# PLD.net
KiCad netlist of a schematic drawn in Altium Designer
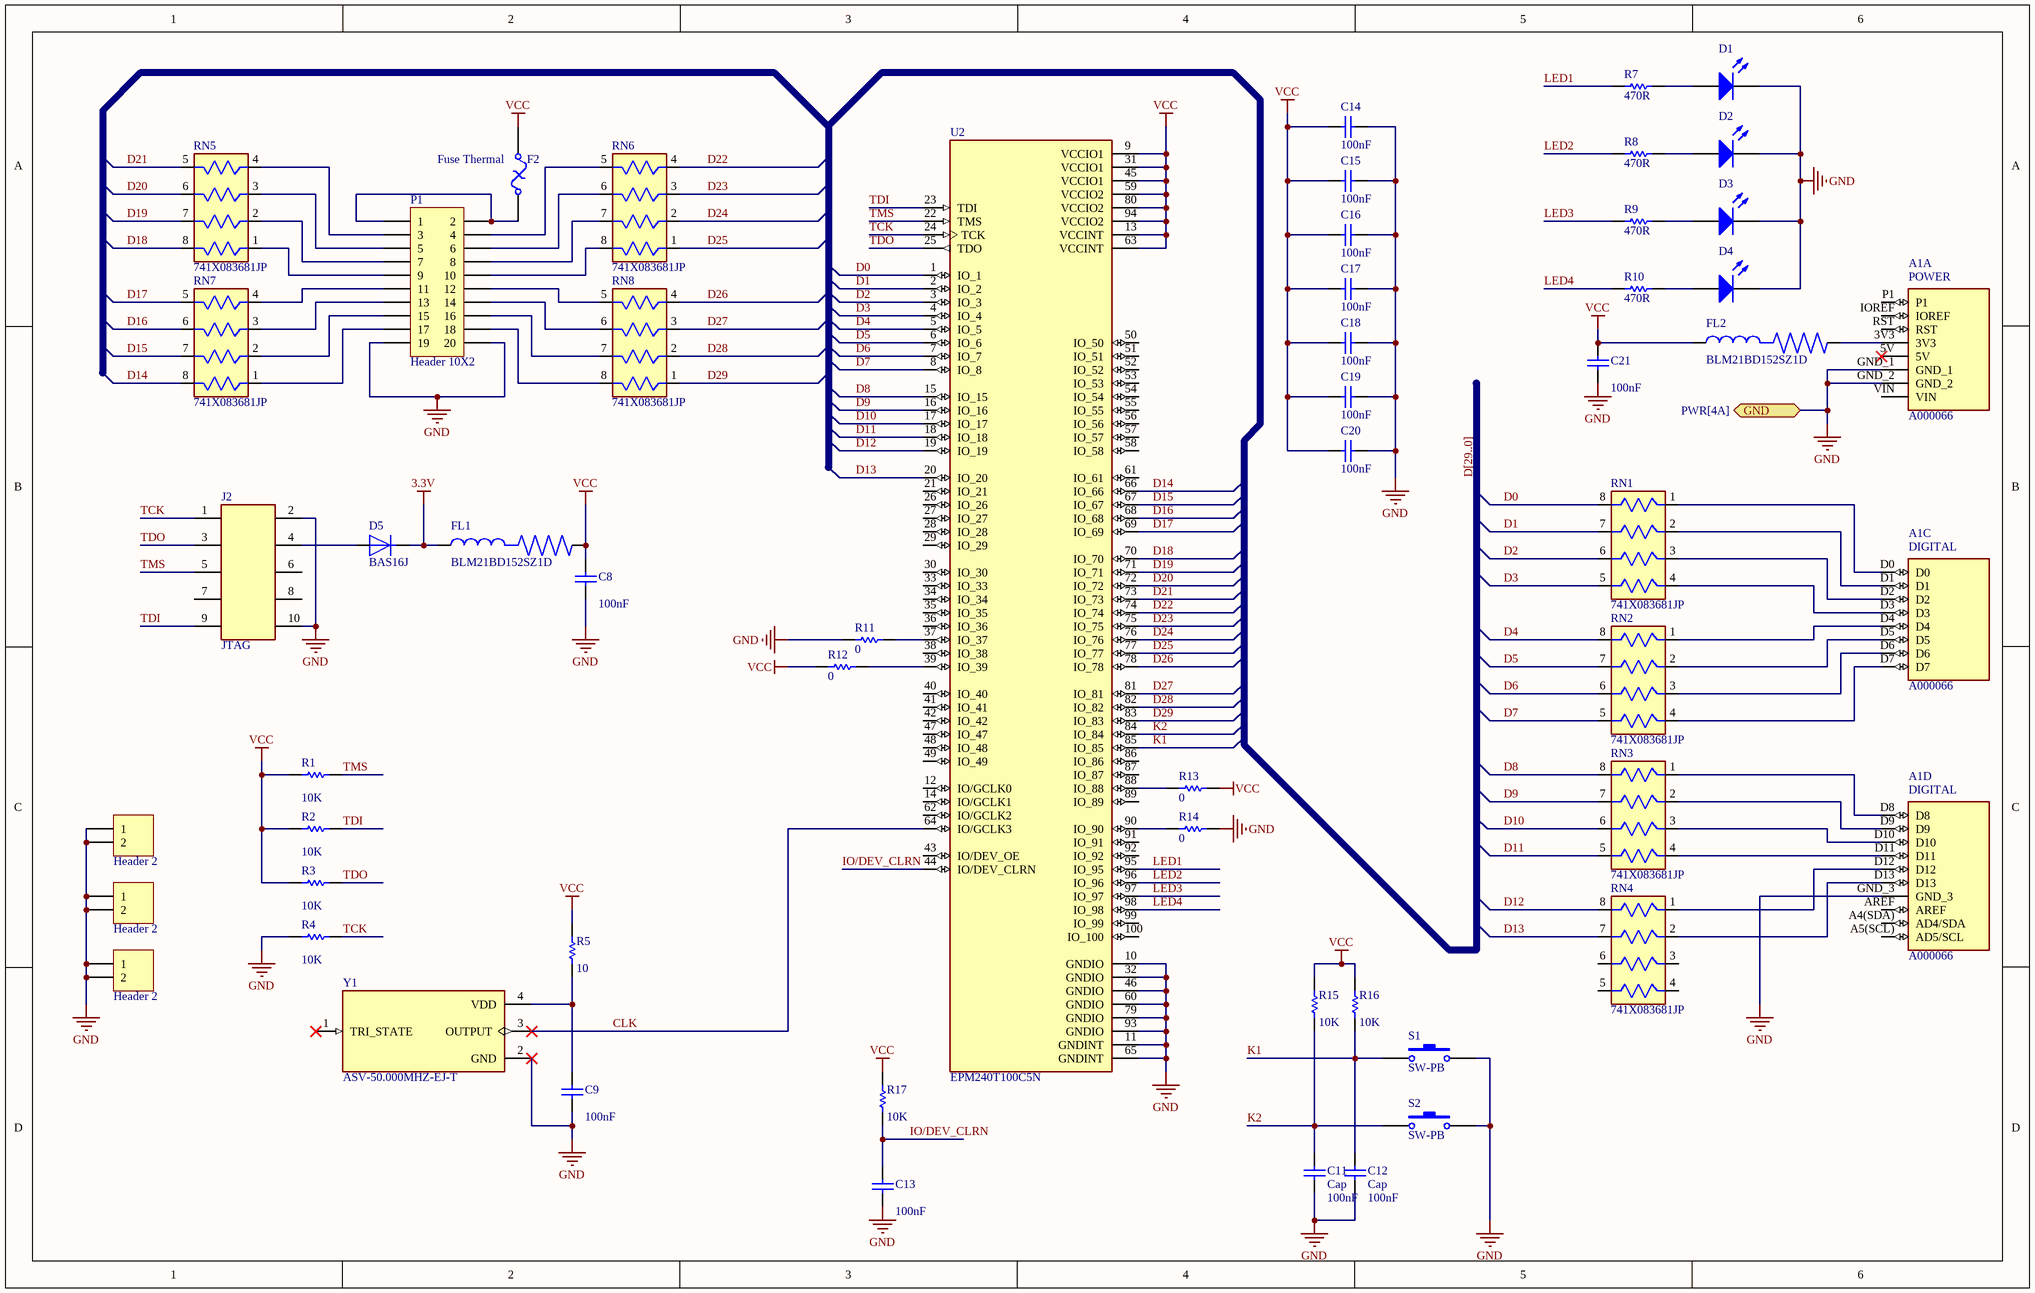
[diagram p0: PLD.SchDoc]

(export (version "E")
  (design (tool "Eeschema 10.0.6"))
  (components
    (comp (ref "A1")
      (value "A000066")
      (footprint "ARDUINO_A000066")
      (description "Microcontroller board based on the ATmega328P")
      (fields (field (name "MP") "ARDUINO UNO REV3 DEVELOPMENT BOARD") (field (name "MF") "Arduino"))
      (libsource (lib "A000066") (part "A000066"))
    )
    (comp (ref "C8")
      (value "100nF")
      (footprint "CAPC1608X90")
      (description "Capacitor")
      (fields (field (name "Comment") "Cap") (field (name "PUBLISHER") "Altium Limited"))
      (libsource (lib "Miscellaneous Devices") (part "Cap"))
    )
    (comp (ref "C9")
      (value "100nF")
      (footprint "CAPC1608X90")
      (description "Capacitor")
      (fields (field (name "Comment") "Cap") (field (name "PUBLISHER") "Altium Limited"))
      (libsource (lib "Miscellaneous Devices") (part "Cap"))
    )
    (comp (ref "C11")
      (value "Cap")
      (footprint "WCAP-CSGP_885012105016")
      (description "Capacitor")
      (fields (field (name "ALTIUM_VALUE") "100nF") (field (name "PUBLISHER") "Altium Limited"))
      (libsource (lib "Miscellaneous Devices") (part "Cap"))
    )
    (comp (ref "C12")
      (value "Cap")
      (footprint "WCAP-CSGP_885012105016")
      (description "Capacitor")
      (fields (field (name "ALTIUM_VALUE") "100nF") (field (name "PUBLISHER") "Altium Limited"))
      (libsource (lib "Miscellaneous Devices") (part "Cap"))
    )
    (comp (ref "C13")
      (value "100nF")
      (footprint "WCAP-CSGP_885012105016")
      (description "Capacitor")
      (fields (field (name "Comment") "Cap") (field (name "PUBLISHER") "Altium Limited"))
      (libsource (lib "Miscellaneous Devices") (part "Cap"))
    )
    (comp (ref "C14")
      (value "100nF")
      (footprint "WCAP-CSGP_885012105016")
      (description "Capacitor")
      (fields (field (name "Comment") "Cap") (field (name "PUBLISHER") "Altium Limited"))
      (libsource (lib "Miscellaneous Devices") (part "Cap"))
    )
    (comp (ref "C15")
      (value "100nF")
      (footprint "WCAP-CSGP_885012105016")
      (description "Capacitor")
      (fields (field (name "Comment") "Cap") (field (name "PUBLISHER") "Altium Limited"))
      (libsource (lib "Miscellaneous Devices") (part "Cap"))
    )
    (comp (ref "C16")
      (value "100nF")
      (footprint "WCAP-CSGP_885012105016")
      (description "Capacitor")
      (fields (field (name "Comment") "Cap") (field (name "PUBLISHER") "Altium Limited"))
      (libsource (lib "Miscellaneous Devices") (part "Cap"))
    )
    (comp (ref "C17")
      (value "100nF")
      (footprint "WCAP-CSGP_885012105016")
      (description "Capacitor")
      (fields (field (name "Comment") "Cap") (field (name "PUBLISHER") "Altium Limited"))
      (libsource (lib "Miscellaneous Devices") (part "Cap"))
    )
    (comp (ref "C18")
      (value "100nF")
      (footprint "WCAP-CSGP_885012105016")
      (description "Capacitor")
      (fields (field (name "Comment") "Cap") (field (name "PUBLISHER") "Altium Limited"))
      (libsource (lib "Miscellaneous Devices") (part "Cap"))
    )
    (comp (ref "C19")
      (value "100nF")
      (footprint "WCAP-CSGP_885012105016")
      (description "Capacitor")
      (fields (field (name "Comment") "Cap") (field (name "PUBLISHER") "Altium Limited"))
      (libsource (lib "Miscellaneous Devices") (part "Cap"))
    )
    (comp (ref "C20")
      (value "100nF")
      (footprint "WCAP-CSGP_885012105016")
      (description "Capacitor")
      (fields (field (name "Comment") "Cap") (field (name "PUBLISHER") "Altium Limited"))
      (libsource (lib "Miscellaneous Devices") (part "Cap"))
    )
    (comp (ref "C21")
      (value "100nF")
      (footprint "CAPC1608X90")
      (description "Capacitor")
      (fields (field (name "Comment") "Cap") (field (name "PUBLISHER") "Altium Limited"))
      (libsource (lib "Miscellaneous Devices") (part "Cap"))
    )
    (comp (ref "D1")
      (value "LED0")
      (footprint "CAPC1608X90")
      (description "Typical INFRARED GaAs LED")
      (fields (field (name "PUBLISHER") "Altium Limited"))
      (libsource (lib "Miscellaneous Devices") (part "LED0"))
    )
    (comp (ref "D2")
      (value "LED0")
      (footprint "CAPC1608X90")
      (description "Typical INFRARED GaAs LED")
      (fields (field (name "PUBLISHER") "Altium Limited"))
      (libsource (lib "Miscellaneous Devices") (part "LED0"))
    )
    (comp (ref "D3")
      (value "LED0")
      (footprint "CAPC1608X90")
      (description "Typical INFRARED GaAs LED")
      (fields (field (name "PUBLISHER") "Altium Limited"))
      (libsource (lib "Miscellaneous Devices") (part "LED0"))
    )
    (comp (ref "D4")
      (value "LED0")
      (footprint "CAPC1608X90")
      (description "Typical INFRARED GaAs LED")
      (fields (field (name "PUBLISHER") "Altium Limited"))
      (libsource (lib "Miscellaneous Devices") (part "LED0"))
    )
    (comp (ref "D5")
      (value "BAS16J")
      (footprint "SOD323F")
      (description "Diode Standard 100V 250mA _DC_ Surface Mount SOD-323F")
      (fields (field (name "MF") "Nexperia USA"))
      (libsource (lib "BAS16J") (part "BAS16J"))
    )
    (comp (ref "F2")
      (value "Fuse Thermal")
      (footprint "C1206")
      (description "Thermal Fuse")
      (fields (field (name "PUBLISHER") "Altium Limited"))
      (libsource (lib "Miscellaneous Devices") (part "Fuse Thermal"))
    )
    (comp (ref "FL1")
      (value "BLM21BD152SZ1D")
      (footprint "C1206")
      (description "1 Ferrite Bead 0805 (2012 Metric) 250mA 450mOhm")
      (fields (field (name "MF") "Murata"))
      (libsource (lib "FB0603") (part "BLM21BD152SZ1D"))
    )
    (comp (ref "FL2")
      (value "BLM21BD152SZ1D")
      (footprint "C1206")
      (description "1 Ferrite Bead 0805 (2012 Metric) 250mA 450mOhm")
      (fields (field (name "MF") "Murata"))
      (libsource (lib "FB0603") (part "BLM21BD152SZ1D"))
    )
    (comp (ref "H2")
      (value "Header 2")
      (footprint "HDR1X2")
      (description "Header, 2-Pin")
      (fields (field (name "PUBLISHER") "Altium Limited"))
      (libsource (lib "Miscellaneous Connectors") (part "Header 2"))
    )
    (comp (ref "H3")
      (value "Header 2")
      (footprint "HDR1X2")
      (description "Header, 2-Pin")
      (fields (field (name "PUBLISHER") "Altium Limited"))
      (libsource (lib "Miscellaneous Connectors") (part "Header 2"))
    )
    (comp (ref "H4")
      (value "Header 2")
      (footprint "HDR1X2")
      (description "Header, 2-Pin")
      (fields (field (name "PUBLISHER") "Altium Limited"))
      (libsource (lib "Miscellaneous Connectors") (part "Header 2"))
    )
    (comp (ref "J2")
      (value "JTAG")
      (footprint "61201021621")
      (description "Connector Header Through Hole 10 position 0.100 _2.54mm_")
      (fields (field (name "MP") "61201021621") (field (name "MF") "Wurth Electronics"))
      (libsource (lib "61201021621") (part "61201021621"))
    )
    (comp (ref "P1")
      (value "Header 10X2")
      (footprint "2002132110020C4LF")
      (description "Header, 10-Pin, Dual row")
      (fields (field (name "PUBLISHER") "Altium Limited"))
      (libsource (lib "Miscellaneous Connectors") (part "Header 10X2"))
    )
    (comp (ref "R1")
      (value "10K")
      (footprint "CAPC1608X90")
      (description "Resistor")
      (fields (field (name "Comment") "Res1") (field (name "PUBLISHER") "Altium Limited"))
      (libsource (lib "Miscellaneous Devices") (part "Res1"))
    )
    (comp (ref "R2")
      (value "10K")
      (footprint "CAPC1608X90")
      (description "Resistor")
      (fields (field (name "Comment") "Res1") (field (name "PUBLISHER") "Altium Limited"))
      (libsource (lib "Miscellaneous Devices") (part "Res1"))
    )
    (comp (ref "R3")
      (value "10K")
      (footprint "CAPC1608X90")
      (description "Resistor")
      (fields (field (name "Comment") "Res1") (field (name "PUBLISHER") "Altium Limited"))
      (libsource (lib "Miscellaneous Devices") (part "Res1"))
    )
    (comp (ref "R4")
      (value "10K")
      (footprint "CAPC1608X90")
      (description "Resistor")
      (fields (field (name "Comment") "Res1") (field (name "PUBLISHER") "Altium Limited"))
      (libsource (lib "Miscellaneous Devices") (part "Res1"))
    )
    (comp (ref "R5")
      (value "10")
      (footprint "CAPC1608X90")
      (description "Resistor")
      (fields (field (name "Comment") "Res1") (field (name "PUBLISHER") "Altium Limited"))
      (libsource (lib "Miscellaneous Devices") (part "Res1"))
    )
    (comp (ref "R7")
      (value "470R")
      (footprint "CAPC1608X90")
      (description "Resistor")
      (fields (field (name "Comment") "Res1") (field (name "PUBLISHER") "Altium Limited"))
      (libsource (lib "Miscellaneous Devices") (part "Res1"))
    )
    (comp (ref "R8")
      (value "470R")
      (footprint "CAPC1608X90")
      (description "Resistor")
      (fields (field (name "Comment") "Res1") (field (name "PUBLISHER") "Altium Limited"))
      (libsource (lib "Miscellaneous Devices") (part "Res1"))
    )
    (comp (ref "R9")
      (value "470R")
      (footprint "CAPC1608X90")
      (description "Resistor")
      (fields (field (name "Comment") "Res1") (field (name "PUBLISHER") "Altium Limited"))
      (libsource (lib "Miscellaneous Devices") (part "Res1"))
    )
    (comp (ref "R10")
      (value "470R")
      (footprint "CAPC1608X90")
      (description "Resistor")
      (fields (field (name "Comment") "Res1") (field (name "PUBLISHER") "Altium Limited"))
      (libsource (lib "Miscellaneous Devices") (part "Res1"))
    )
    (comp (ref "R11")
      (value "0")
      (footprint "WCAP-CSGP_885012105016")
      (description "Resistor")
      (fields (field (name "Comment") "Res1") (field (name "PUBLISHER") "Altium Limited"))
      (libsource (lib "Miscellaneous Devices") (part "Res1"))
    )
    (comp (ref "R12")
      (value "0")
      (footprint "WCAP-CSGP_885012105016")
      (description "Resistor")
      (fields (field (name "Comment") "Res1") (field (name "PUBLISHER") "Altium Limited"))
      (libsource (lib "Miscellaneous Devices") (part "Res1"))
    )
    (comp (ref "R13")
      (value "0")
      (footprint "WCAP-CSGP_885012105016")
      (description "Resistor")
      (fields (field (name "Comment") "Res1") (field (name "PUBLISHER") "Altium Limited"))
      (libsource (lib "Miscellaneous Devices") (part "Res1"))
    )
    (comp (ref "R14")
      (value "0")
      (footprint "WCAP-CSGP_885012105016")
      (description "Resistor")
      (fields (field (name "Comment") "Res1") (field (name "PUBLISHER") "Altium Limited"))
      (libsource (lib "Miscellaneous Devices") (part "Res1"))
    )
    (comp (ref "R15")
      (value "10K")
      (footprint "WCAP-CSGP_885012105016")
      (description "Resistor")
      (fields (field (name "Comment") "Res1") (field (name "PUBLISHER") "Altium Limited"))
      (libsource (lib "Miscellaneous Devices") (part "Res1"))
    )
    (comp (ref "R16")
      (value "10K")
      (footprint "WCAP-CSGP_885012105016")
      (description "Resistor")
      (fields (field (name "Comment") "Res1") (field (name "PUBLISHER") "Altium Limited"))
      (libsource (lib "Miscellaneous Devices") (part "Res1"))
    )
    (comp (ref "R17")
      (value "10K")
      (footprint "WCAP-CSGP_885012105016")
      (description "Resistor")
      (fields (field (name "Comment") "Res1") (field (name "PUBLISHER") "Altium Limited"))
      (libsource (lib "Miscellaneous Devices") (part "Res1"))
    )
    (comp (ref "RN1")
      (value "741X083681JP")
      (footprint "RESCAXS50P200X100X45_8N")
      (description "Resistor Networks & Arrays 680ohms 5% Isolated")
      (fields (field (name "MF") "CTS Components"))
      (libsource (lib "741X083681JP") (part "741X083681JP"))
    )
    (comp (ref "RN2")
      (value "741X083681JP")
      (footprint "RESCAXS50P200X100X45_8N")
      (description "Resistor Networks & Arrays 680ohms 5% Isolated")
      (fields (field (name "MF") "CTS Components"))
      (libsource (lib "741X083681JP") (part "741X083681JP"))
    )
    (comp (ref "RN3")
      (value "741X083681JP")
      (footprint "RESCAXS50P200X100X45_8N")
      (description "Resistor Networks & Arrays 680ohms 5% Isolated")
      (fields (field (name "MF") "CTS Components"))
      (libsource (lib "741X083681JP") (part "741X083681JP"))
    )
    (comp (ref "RN4")
      (value "741X083681JP")
      (footprint "RESCAXS50P200X100X45_8N")
      (description "Resistor Networks & Arrays 680ohms 5% Isolated")
      (fields (field (name "MF") "CTS Components"))
      (libsource (lib "741X083681JP") (part "741X083681JP"))
    )
    (comp (ref "RN5")
      (value "741X083681JP")
      (footprint "RESCAXS50P200X100X45_8N")
      (description "Resistor Networks & Arrays 680ohms 5% Isolated")
      (fields (field (name "MF") "CTS Components"))
      (libsource (lib "") (part "741X083681JP_1"))
    )
    (comp (ref "RN6")
      (value "741X083681JP")
      (footprint "RESCAXS50P200X100X45_8N")
      (description "Resistor Networks & Arrays 680ohms 5% Isolated")
      (fields (field (name "MF") "CTS Components"))
      (libsource (lib "") (part "741X083681JP_1"))
    )
    (comp (ref "RN7")
      (value "741X083681JP")
      (footprint "RESCAXS50P200X100X45_8N")
      (description "Resistor Networks & Arrays 680ohms 5% Isolated")
      (fields (field (name "MF") "CTS Components"))
      (libsource (lib "") (part "741X083681JP_1"))
    )
    (comp (ref "RN8")
      (value "741X083681JP")
      (footprint "RESCAXS50P200X100X45_8N")
      (description "Resistor Networks & Arrays 680ohms 5% Isolated")
      (fields (field (name "MF") "CTS Components"))
      (libsource (lib "") (part "741X083681JP_1"))
    )
    (comp (ref "S1")
      (value "SW-PB")
      (footprint "SW_4.5X4.5")
      (description "Switch")
      (fields (field (name "PUBLISHER") "Altium Limited"))
      (libsource (lib "Miscellaneous Devices") (part "SW-PB"))
    )
    (comp (ref "S2")
      (value "SW-PB")
      (footprint "SW_4.5X4.5")
      (description "Switch")
      (fields (field (name "PUBLISHER") "Altium Limited"))
      (libsource (lib "Miscellaneous Devices") (part "SW-PB"))
    )
    (comp (ref "U2")
      (value "EPM240T100C5N")
      (footprint "QFP50P1600X1600X120-100N")
      (description "IC CPLD 192MC 4.7NS 100TQFP")
      (fields (field (name "MF") "Intel"))
      (libsource (lib "EPM240T100C5N") (part "EPM240T100C5N"))
    )
    (comp (ref "Y1")
      (value "ASV-50.000MHZ-EJ-T")
      (footprint "XTAL_ASV-50.000MHZ-EJ-T")
      (libsource (lib "ASV-50.000MHZ-EJ-T") (part "ASV-50.000MHZ-EJ-T"))
    )
  )
  (nets
    (net (code "1") (name "/CLK") (class "Default")
      (node (ref "U2") (pin "64") (pinfunction "IO/GCLK3_64") (pintype "bidirectional"))
      (node (ref "Y1") (pin "3") (pinfunction "OUTPUT_3") (pintype "output"))
    )
    (net (code "2") (name "/D0") (class "Default")
      (node (ref "RN1") (pin "8") (pinfunction "8_8") (pintype "passive"))
      (node (ref "U2") (pin "1") (pinfunction "IO_1_1") (pintype "bidirectional"))
    )
    (net (code "3") (name "/D1") (class "Default")
      (node (ref "RN1") (pin "7") (pinfunction "7_7") (pintype "passive"))
      (node (ref "U2") (pin "2") (pinfunction "IO_2_2") (pintype "bidirectional"))
    )
    (net (code "4") (name "/D2") (class "Default")
      (node (ref "RN1") (pin "6") (pinfunction "6_6") (pintype "passive"))
      (node (ref "U2") (pin "3") (pinfunction "IO_3_3") (pintype "bidirectional"))
    )
    (net (code "5") (name "/D3") (class "Default")
      (node (ref "RN1") (pin "5") (pinfunction "5_5") (pintype "passive"))
      (node (ref "U2") (pin "4") (pinfunction "IO_4_4") (pintype "bidirectional"))
    )
    (net (code "6") (name "/D4") (class "Default")
      (node (ref "RN2") (pin "8") (pinfunction "8_8") (pintype "passive"))
      (node (ref "U2") (pin "5") (pinfunction "IO_5_5") (pintype "bidirectional"))
    )
    (net (code "7") (name "/D5") (class "Default")
      (node (ref "RN2") (pin "7") (pinfunction "7_7") (pintype "passive"))
      (node (ref "U2") (pin "6") (pinfunction "IO_6_6") (pintype "bidirectional"))
    )
    (net (code "8") (name "/D6") (class "Default")
      (node (ref "RN2") (pin "6") (pinfunction "6_6") (pintype "passive"))
      (node (ref "U2") (pin "7") (pinfunction "IO_7_7") (pintype "bidirectional"))
    )
    (net (code "9") (name "/D7") (class "Default")
      (node (ref "RN2") (pin "5") (pinfunction "5_5") (pintype "passive"))
      (node (ref "U2") (pin "8") (pinfunction "IO_8_8") (pintype "bidirectional"))
    )
    (net (code "10") (name "/D8") (class "Default")
      (node (ref "RN3") (pin "8") (pinfunction "8_8") (pintype "passive"))
      (node (ref "U2") (pin "15") (pinfunction "IO_15_15") (pintype "bidirectional"))
    )
    (net (code "11") (name "/D9") (class "Default")
      (node (ref "RN3") (pin "7") (pinfunction "7_7") (pintype "passive"))
      (node (ref "U2") (pin "16") (pinfunction "IO_16_16") (pintype "bidirectional"))
    )
    (net (code "12") (name "/D10") (class "Default")
      (node (ref "RN3") (pin "6") (pinfunction "6_6") (pintype "passive"))
      (node (ref "U2") (pin "17") (pinfunction "IO_17_17") (pintype "bidirectional"))
    )
    (net (code "13") (name "/D11") (class "Default")
      (node (ref "RN3") (pin "5") (pinfunction "5_5") (pintype "passive"))
      (node (ref "U2") (pin "18") (pinfunction "IO_18_18") (pintype "bidirectional"))
    )
    (net (code "14") (name "/D12") (class "Default")
      (node (ref "RN4") (pin "8") (pinfunction "8_8") (pintype "passive"))
      (node (ref "U2") (pin "19") (pinfunction "IO_19_19") (pintype "bidirectional"))
    )
    (net (code "15") (name "/D13") (class "Default")
      (node (ref "RN4") (pin "7") (pinfunction "7_7") (pintype "passive"))
      (node (ref "U2") (pin "20") (pinfunction "IO_20_20") (pintype "bidirectional"))
    )
    (net (code "16") (name "/D14") (class "Default")
      (node (ref "RN7") (pin "8") (pinfunction "8_8") (pintype "passive"))
      (node (ref "U2") (pin "66") (pinfunction "IO_66_66") (pintype "bidirectional"))
    )
    (net (code "17") (name "/D15") (class "Default")
      (node (ref "RN7") (pin "7") (pinfunction "7_7") (pintype "passive"))
      (node (ref "U2") (pin "67") (pinfunction "IO_67_67") (pintype "bidirectional"))
    )
    (net (code "18") (name "/D16") (class "Default")
      (node (ref "RN7") (pin "6") (pinfunction "6_6") (pintype "passive"))
      (node (ref "U2") (pin "68") (pinfunction "IO_68_68") (pintype "bidirectional"))
    )
    (net (code "19") (name "/D17") (class "Default")
      (node (ref "RN7") (pin "5") (pinfunction "5_5") (pintype "passive"))
      (node (ref "U2") (pin "69") (pinfunction "IO_69_69") (pintype "bidirectional"))
    )
    (net (code "20") (name "/D18") (class "Default")
      (node (ref "RN5") (pin "8") (pinfunction "8_8") (pintype "passive"))
      (node (ref "U2") (pin "70") (pinfunction "IO_70_70") (pintype "bidirectional"))
    )
    (net (code "21") (name "/D19") (class "Default")
      (node (ref "RN5") (pin "7") (pinfunction "7_7") (pintype "passive"))
      (node (ref "U2") (pin "71") (pinfunction "IO_71_71") (pintype "bidirectional"))
    )
    (net (code "22") (name "/D20") (class "Default")
      (node (ref "RN5") (pin "6") (pinfunction "6_6") (pintype "passive"))
      (node (ref "U2") (pin "72") (pinfunction "IO_72_72") (pintype "bidirectional"))
    )
    (net (code "23") (name "/D21") (class "Default")
      (node (ref "RN5") (pin "5") (pinfunction "5_5") (pintype "passive"))
      (node (ref "U2") (pin "73") (pinfunction "IO_73_73") (pintype "bidirectional"))
    )
    (net (code "24") (name "/D22") (class "Default")
      (node (ref "RN6") (pin "4") (pinfunction "4_4") (pintype "passive"))
      (node (ref "U2") (pin "74") (pinfunction "IO_74_74") (pintype "bidirectional"))
    )
    (net (code "25") (name "/D23") (class "Default")
      (node (ref "RN6") (pin "3") (pinfunction "3_3") (pintype "passive"))
      (node (ref "U2") (pin "75") (pinfunction "IO_75_75") (pintype "bidirectional"))
    )
    (net (code "26") (name "/D24") (class "Default")
      (node (ref "RN6") (pin "2") (pinfunction "2_2") (pintype "passive"))
      (node (ref "U2") (pin "76") (pinfunction "IO_76_76") (pintype "bidirectional"))
    )
    (net (code "27") (name "/D25") (class "Default")
      (node (ref "RN6") (pin "1") (pinfunction "1_1") (pintype "passive"))
      (node (ref "U2") (pin "77") (pinfunction "IO_77_77") (pintype "bidirectional"))
    )
    (net (code "28") (name "/D26") (class "Default")
      (node (ref "RN8") (pin "4") (pinfunction "4_4") (pintype "passive"))
      (node (ref "U2") (pin "78") (pinfunction "IO_78_78") (pintype "bidirectional"))
    )
    (net (code "29") (name "/D27") (class "Default")
      (node (ref "RN8") (pin "3") (pinfunction "3_3") (pintype "passive"))
      (node (ref "U2") (pin "81") (pinfunction "IO_81_81") (pintype "bidirectional"))
    )
    (net (code "30") (name "/D28") (class "Default")
      (node (ref "RN8") (pin "2") (pinfunction "2_2") (pintype "passive"))
      (node (ref "U2") (pin "82") (pinfunction "IO_82_82") (pintype "bidirectional"))
    )
    (net (code "31") (name "/D29") (class "Default")
      (node (ref "RN8") (pin "1") (pinfunction "1_1") (pintype "passive"))
      (node (ref "U2") (pin "83") (pinfunction "IO_83_83") (pintype "bidirectional"))
    )
    (net (code "33") (name "/IO{slash}DEV_CLRN") (class "Default")
      (node (ref "C13") (pin "2") (pinfunction "2_2") (pintype "passive"))
      (node (ref "R17") (pin "1") (pinfunction "1_1") (pintype "passive"))
      (node (ref "U2") (pin "44") (pinfunction "IO/DEV_CLRN_44") (pintype "bidirectional"))
    )
    (net (code "34") (name "/K1") (class "Default")
      (node (ref "C12") (pin "2") (pinfunction "2_2") (pintype "passive"))
      (node (ref "R16") (pin "1") (pinfunction "1_1") (pintype "passive"))
      (node (ref "S1") (pin "1") (pinfunction "1_1") (pintype "passive"))
      (node (ref "U2") (pin "85") (pinfunction "IO_85_85") (pintype "bidirectional"))
    )
    (net (code "35") (name "/K2") (class "Default")
      (node (ref "C11") (pin "2") (pinfunction "2_2") (pintype "passive"))
      (node (ref "R15") (pin "1") (pinfunction "1_1") (pintype "passive"))
      (node (ref "S2") (pin "1") (pinfunction "1_1") (pintype "passive"))
      (node (ref "U2") (pin "84") (pinfunction "IO_84_84") (pintype "bidirectional"))
    )
    (net (code "36") (name "/LED1") (class "Default")
      (node (ref "R7") (pin "2") (pinfunction "2_2") (pintype "passive"))
      (node (ref "U2") (pin "95") (pinfunction "IO_95_95") (pintype "bidirectional"))
    )
    (net (code "37") (name "/LED2") (class "Default")
      (node (ref "R8") (pin "2") (pinfunction "2_2") (pintype "passive"))
      (node (ref "U2") (pin "96") (pinfunction "IO_96_96") (pintype "bidirectional"))
    )
    (net (code "38") (name "/LED3") (class "Default")
      (node (ref "R9") (pin "2") (pinfunction "2_2") (pintype "passive"))
      (node (ref "U2") (pin "97") (pinfunction "IO_97_97") (pintype "bidirectional"))
    )
    (net (code "39") (name "/LED4") (class "Default")
      (node (ref "R10") (pin "2") (pinfunction "2_2") (pintype "passive"))
      (node (ref "U2") (pin "98") (pinfunction "IO_98_98") (pintype "bidirectional"))
    )
    (net (code "40") (name "/TCK") (class "Default")
      (node (ref "J2") (pin "1") (pinfunction "1_1") (pintype "passive"))
      (node (ref "R4") (pin "2") (pinfunction "2_2") (pintype "passive"))
      (node (ref "U2") (pin "24") (pinfunction "TCK_24") (pintype "input"))
    )
    (net (code "41") (name "/TDI") (class "Default")
      (node (ref "J2") (pin "9") (pinfunction "9_9") (pintype "passive"))
      (node (ref "R2") (pin "2") (pinfunction "2_2") (pintype "passive"))
      (node (ref "U2") (pin "23") (pinfunction "TDI_23") (pintype "input"))
    )
    (net (code "42") (name "/TDO") (class "Default")
      (node (ref "J2") (pin "3") (pinfunction "3_3") (pintype "passive"))
      (node (ref "R3") (pin "2") (pinfunction "2_2") (pintype "passive"))
      (node (ref "U2") (pin "25") (pinfunction "TDO_25") (pintype "output"))
    )
    (net (code "43") (name "/TMS") (class "Default")
      (node (ref "J2") (pin "5") (pinfunction "5_5") (pintype "passive"))
      (node (ref "R1") (pin "2") (pinfunction "2_2") (pintype "passive"))
      (node (ref "U2") (pin "22") (pinfunction "TMS_22") (pintype "input"))
    )
    (net (code "44") (name "3.3V") (class "Default")
      (node (ref "D5") (pin "1") (pinfunction "K_1") (pintype "passive"))
      (node (ref "FL1") (pin "1") (pinfunction "1_1") (pintype "passive"))
    )
    (net (code "45") (name "GND") (class "Default")
      (node (ref "A1") (pin "GND_1") (pinfunction "GND_1_GND_1") (pintype "power_in"))
      (node (ref "A1") (pin "GND_2") (pinfunction "GND_2_GND_2") (pintype "power_in"))
      (node (ref "A1") (pin "GND_3") (pinfunction "GND_3_GND_3") (pintype "power_in"))
      (node (ref "C11") (pin "1") (pinfunction "1_1") (pintype "passive"))
      (node (ref "C12") (pin "1") (pinfunction "1_1") (pintype "passive"))
      (node (ref "C13") (pin "1") (pinfunction "1_1") (pintype "passive"))
      (node (ref "C14") (pin "1") (pinfunction "1_1") (pintype "passive"))
      (node (ref "C15") (pin "1") (pinfunction "1_1") (pintype "passive"))
      (node (ref "C16") (pin "1") (pinfunction "1_1") (pintype "passive"))
      (node (ref "C17") (pin "1") (pinfunction "1_1") (pintype "passive"))
      (node (ref "C18") (pin "1") (pinfunction "1_1") (pintype "passive"))
      (node (ref "C19") (pin "1") (pinfunction "1_1") (pintype "passive"))
      (node (ref "C20") (pin "1") (pinfunction "1_1") (pintype "passive"))
      (node (ref "C21") (pin "1") (pinfunction "1_1") (pintype "passive"))
      (node (ref "C8") (pin "1") (pinfunction "1_1") (pintype "passive"))
      (node (ref "C9") (pin "1") (pinfunction "1_1") (pintype "passive"))
      (node (ref "D1") (pin "2") (pinfunction "K_2") (pintype "passive"))
      (node (ref "D2") (pin "2") (pinfunction "K_2") (pintype "passive"))
      (node (ref "D3") (pin "2") (pinfunction "K_2") (pintype "passive"))
      (node (ref "D4") (pin "2") (pinfunction "K_2") (pintype "passive"))
      (node (ref "H2") (pin "1") (pinfunction "1_1") (pintype "passive"))
      (node (ref "H2") (pin "2") (pinfunction "2_2") (pintype "passive"))
      (node (ref "H3") (pin "1") (pinfunction "1_1") (pintype "passive"))
      (node (ref "H3") (pin "2") (pinfunction "2_2") (pintype "passive"))
      (node (ref "H4") (pin "1") (pinfunction "1_1") (pintype "passive"))
      (node (ref "H4") (pin "2") (pinfunction "2_2") (pintype "passive"))
      (node (ref "J2") (pin "10") (pinfunction "10_10") (pintype "passive"))
      (node (ref "J2") (pin "2") (pinfunction "2_2") (pintype "passive"))
      (node (ref "P1") (pin "19") (pinfunction "19_19") (pintype "passive"))
      (node (ref "P1") (pin "20") (pinfunction "20_20") (pintype "passive"))
      (node (ref "R11") (pin "2") (pinfunction "2_2") (pintype "passive"))
      (node (ref "R14") (pin "1") (pinfunction "1_1") (pintype "passive"))
      (node (ref "R4") (pin "1") (pinfunction "1_1") (pintype "passive"))
      (node (ref "S1") (pin "2") (pinfunction "2_2") (pintype "passive"))
      (node (ref "S2") (pin "2") (pinfunction "2_2") (pintype "passive"))
      (node (ref "U2") (pin "10") (pinfunction "GNDIO_10") (pintype "power_in"))
      (node (ref "U2") (pin "11") (pinfunction "GNDINT_11") (pintype "power_in"))
      (node (ref "U2") (pin "32") (pinfunction "GNDIO_32") (pintype "power_in"))
      (node (ref "U2") (pin "46") (pinfunction "GNDIO_46") (pintype "power_in"))
      (node (ref "U2") (pin "60") (pinfunction "GNDIO_60") (pintype "power_in"))
      (node (ref "U2") (pin "65") (pinfunction "GNDINT_65") (pintype "power_in"))
      (node (ref "U2") (pin "79") (pinfunction "GNDIO_79") (pintype "power_in"))
      (node (ref "U2") (pin "93") (pinfunction "GNDIO_93") (pintype "power_in"))
      (node (ref "Y1") (pin "2") (pinfunction "GND_2") (pintype "power_in"))
    )
    (net (code "46") (name "Net-(A1-Pad3V3)") (class "Default")
      (node (ref "A1") (pin "3V3") (pinfunction "3V3_3V3") (pintype "power_in"))
      (node (ref "FL2") (pin "2") (pinfunction "2_2") (pintype "passive"))
    )
    (net (code "47") (name "Net-(A1-PadD0)") (class "Default")
      (node (ref "A1") (pin "D0") (pinfunction "D0_D0") (pintype "bidirectional"))
      (node (ref "RN1") (pin "1") (pinfunction "1_1") (pintype "passive"))
    )
    (net (code "48") (name "Net-(A1-PadD1)") (class "Default")
      (node (ref "A1") (pin "D1") (pinfunction "D1_D1") (pintype "bidirectional"))
      (node (ref "RN1") (pin "2") (pinfunction "2_2") (pintype "passive"))
    )
    (net (code "49") (name "Net-(A1-PadD2)") (class "Default")
      (node (ref "A1") (pin "D2") (pinfunction "D2_D2") (pintype "bidirectional"))
      (node (ref "RN1") (pin "3") (pinfunction "3_3") (pintype "passive"))
    )
    (net (code "50") (name "Net-(A1-PadD3)") (class "Default")
      (node (ref "A1") (pin "D3") (pinfunction "D3_D3") (pintype "bidirectional"))
      (node (ref "RN1") (pin "4") (pinfunction "4_4") (pintype "passive"))
    )
    (net (code "51") (name "Net-(A1-PadD4)") (class "Default")
      (node (ref "A1") (pin "D4") (pinfunction "D4_D4") (pintype "bidirectional"))
      (node (ref "RN2") (pin "1") (pinfunction "1_1") (pintype "passive"))
    )
    (net (code "52") (name "Net-(A1-PadD5)") (class "Default")
      (node (ref "A1") (pin "D5") (pinfunction "D5_D5") (pintype "bidirectional"))
      (node (ref "RN2") (pin "2") (pinfunction "2_2") (pintype "passive"))
    )
    (net (code "53") (name "Net-(A1-PadD6)") (class "Default")
      (node (ref "A1") (pin "D6") (pinfunction "D6_D6") (pintype "bidirectional"))
      (node (ref "RN2") (pin "3") (pinfunction "3_3") (pintype "passive"))
    )
    (net (code "54") (name "Net-(A1-PadD7)") (class "Default")
      (node (ref "A1") (pin "D7") (pinfunction "D7_D7") (pintype "bidirectional"))
      (node (ref "RN2") (pin "4") (pinfunction "4_4") (pintype "passive"))
    )
    (net (code "55") (name "Net-(A1-PadD8)") (class "Default")
      (node (ref "A1") (pin "D8") (pinfunction "D8_D8") (pintype "bidirectional"))
      (node (ref "RN3") (pin "1") (pinfunction "1_1") (pintype "passive"))
    )
    (net (code "56") (name "Net-(A1-PadD9)") (class "Default")
      (node (ref "A1") (pin "D9") (pinfunction "D9_D9") (pintype "bidirectional"))
      (node (ref "RN3") (pin "2") (pinfunction "2_2") (pintype "passive"))
    )
    (net (code "57") (name "Net-(A1-PadD10)") (class "Default")
      (node (ref "A1") (pin "D10") (pinfunction "D10_D10") (pintype "bidirectional"))
      (node (ref "RN3") (pin "3") (pinfunction "3_3") (pintype "passive"))
    )
    (net (code "58") (name "Net-(A1-PadD11)") (class "Default")
      (node (ref "A1") (pin "D11") (pinfunction "D11_D11") (pintype "bidirectional"))
      (node (ref "RN3") (pin "4") (pinfunction "4_4") (pintype "passive"))
    )
    (net (code "59") (name "Net-(A1-PadD12)") (class "Default")
      (node (ref "A1") (pin "D12") (pinfunction "D12_D12") (pintype "bidirectional"))
      (node (ref "RN4") (pin "1") (pinfunction "1_1") (pintype "passive"))
    )
    (net (code "60") (name "Net-(A1-PadD13)") (class "Default")
      (node (ref "A1") (pin "D13") (pinfunction "D13_D13") (pintype "bidirectional"))
      (node (ref "RN4") (pin "2") (pinfunction "2_2") (pintype "passive"))
    )
    (net (code "61") (name "Net-(D1-A)") (class "Default")
      (node (ref "D1") (pin "1") (pinfunction "A_1") (pintype "passive"))
      (node (ref "R7") (pin "1") (pinfunction "1_1") (pintype "passive"))
    )
    (net (code "62") (name "Net-(D2-A)") (class "Default")
      (node (ref "D2") (pin "1") (pinfunction "A_1") (pintype "passive"))
      (node (ref "R8") (pin "1") (pinfunction "1_1") (pintype "passive"))
    )
    (net (code "63") (name "Net-(D3-A)") (class "Default")
      (node (ref "D3") (pin "1") (pinfunction "A_1") (pintype "passive"))
      (node (ref "R9") (pin "1") (pinfunction "1_1") (pintype "passive"))
    )
    (net (code "64") (name "Net-(D4-A)") (class "Default")
      (node (ref "D4") (pin "1") (pinfunction "A_1") (pintype "passive"))
      (node (ref "R10") (pin "1") (pinfunction "1_1") (pintype "passive"))
    )
    (net (code "65") (name "Net-(D5-A)") (class "Default")
      (node (ref "D5") (pin "2") (pinfunction "A_2") (pintype "passive"))
      (node (ref "J2") (pin "4") (pinfunction "4_4") (pintype "passive"))
    )
    (net (code "66") (name "Net-(F2-Pad1)") (class "Default")
      (node (ref "F2") (pin "1") (pinfunction "1_1") (pintype "passive"))
      (node (ref "P1") (pin "1") (pinfunction "1_1") (pintype "passive"))
      (node (ref "P1") (pin "2") (pinfunction "2_2") (pintype "passive"))
    )
    (net (code "67") (name "Net-(P1-Pad3)") (class "Default")
      (node (ref "P1") (pin "3") (pinfunction "3_3") (pintype "passive"))
      (node (ref "RN5") (pin "4") (pinfunction "4_4") (pintype "passive"))
    )
    (net (code "68") (name "Net-(P1-Pad4)") (class "Default")
      (node (ref "P1") (pin "4") (pinfunction "4_4") (pintype "passive"))
      (node (ref "RN6") (pin "5") (pinfunction "5_5") (pintype "passive"))
    )
    (net (code "69") (name "Net-(P1-Pad5)") (class "Default")
      (node (ref "P1") (pin "5") (pinfunction "5_5") (pintype "passive"))
      (node (ref "RN5") (pin "3") (pinfunction "3_3") (pintype "passive"))
    )
    (net (code "70") (name "Net-(P1-Pad6)") (class "Default")
      (node (ref "P1") (pin "6") (pinfunction "6_6") (pintype "passive"))
      (node (ref "RN6") (pin "6") (pinfunction "6_6") (pintype "passive"))
    )
    (net (code "71") (name "Net-(P1-Pad7)") (class "Default")
      (node (ref "P1") (pin "7") (pinfunction "7_7") (pintype "passive"))
      (node (ref "RN5") (pin "2") (pinfunction "2_2") (pintype "passive"))
    )
    (net (code "72") (name "Net-(P1-Pad8)") (class "Default")
      (node (ref "P1") (pin "8") (pinfunction "8_8") (pintype "passive"))
      (node (ref "RN6") (pin "7") (pinfunction "7_7") (pintype "passive"))
    )
    (net (code "73") (name "Net-(P1-Pad9)") (class "Default")
      (node (ref "P1") (pin "9") (pinfunction "9_9") (pintype "passive"))
      (node (ref "RN5") (pin "1") (pinfunction "1_1") (pintype "passive"))
    )
    (net (code "74") (name "Net-(P1-Pad10)") (class "Default")
      (node (ref "P1") (pin "10") (pinfunction "10_10") (pintype "passive"))
      (node (ref "RN6") (pin "8") (pinfunction "8_8") (pintype "passive"))
    )
    (net (code "75") (name "Net-(P1-Pad11)") (class "Default")
      (node (ref "P1") (pin "11") (pinfunction "11_11") (pintype "passive"))
      (node (ref "RN7") (pin "4") (pinfunction "4_4") (pintype "passive"))
    )
    (net (code "76") (name "Net-(P1-Pad12)") (class "Default")
      (node (ref "P1") (pin "12") (pinfunction "12_12") (pintype "passive"))
      (node (ref "RN8") (pin "5") (pinfunction "5_5") (pintype "passive"))
    )
    (net (code "77") (name "Net-(P1-Pad13)") (class "Default")
      (node (ref "P1") (pin "13") (pinfunction "13_13") (pintype "passive"))
      (node (ref "RN7") (pin "3") (pinfunction "3_3") (pintype "passive"))
    )
    (net (code "78") (name "Net-(P1-Pad14)") (class "Default")
      (node (ref "P1") (pin "14") (pinfunction "14_14") (pintype "passive"))
      (node (ref "RN8") (pin "6") (pinfunction "6_6") (pintype "passive"))
    )
    (net (code "79") (name "Net-(P1-Pad15)") (class "Default")
      (node (ref "P1") (pin "15") (pinfunction "15_15") (pintype "passive"))
      (node (ref "RN7") (pin "2") (pinfunction "2_2") (pintype "passive"))
    )
    (net (code "80") (name "Net-(P1-Pad16)") (class "Default")
      (node (ref "P1") (pin "16") (pinfunction "16_16") (pintype "passive"))
      (node (ref "RN8") (pin "7") (pinfunction "7_7") (pintype "passive"))
    )
    (net (code "81") (name "Net-(P1-Pad17)") (class "Default")
      (node (ref "P1") (pin "17") (pinfunction "17_17") (pintype "passive"))
      (node (ref "RN7") (pin "1") (pinfunction "1_1") (pintype "passive"))
    )
    (net (code "82") (name "Net-(P1-Pad18)") (class "Default")
      (node (ref "P1") (pin "18") (pinfunction "18_18") (pintype "passive"))
      (node (ref "RN8") (pin "8") (pinfunction "8_8") (pintype "passive"))
    )
    (net (code "83") (name "Net-(U2-IO_37)") (class "Default")
      (node (ref "R11") (pin "1") (pinfunction "1_1") (pintype "passive"))
      (node (ref "U2") (pin "37") (pinfunction "IO_37_37") (pintype "bidirectional"))
    )
    (net (code "84") (name "Net-(U2-IO_39)") (class "Default")
      (node (ref "R12") (pin "1") (pinfunction "1_1") (pintype "passive"))
      (node (ref "U2") (pin "39") (pinfunction "IO_39_39") (pintype "bidirectional"))
    )
    (net (code "85") (name "Net-(U2-IO_88)") (class "Default")
      (node (ref "R13") (pin "2") (pinfunction "2_2") (pintype "passive"))
      (node (ref "U2") (pin "88") (pinfunction "IO_88_88") (pintype "bidirectional"))
    )
    (net (code "86") (name "Net-(U2-IO_90)") (class "Default")
      (node (ref "R14") (pin "2") (pinfunction "2_2") (pintype "passive"))
      (node (ref "U2") (pin "90") (pinfunction "IO_90_90") (pintype "bidirectional"))
    )
    (net (code "87") (name "Net-(Y1-VDD)") (class "Default")
      (node (ref "C9") (pin "2") (pinfunction "2_2") (pintype "passive"))
      (node (ref "R5") (pin "1") (pinfunction "1_1") (pintype "passive"))
      (node (ref "Y1") (pin "4") (pinfunction "VDD_4") (pintype "power_in"))
    )
    (net (code "88") (name "VCC") (class "Default")
      (node (ref "C14") (pin "2") (pinfunction "2_2") (pintype "passive"))
      (node (ref "C15") (pin "2") (pinfunction "2_2") (pintype "passive"))
      (node (ref "C16") (pin "2") (pinfunction "2_2") (pintype "passive"))
      (node (ref "C17") (pin "2") (pinfunction "2_2") (pintype "passive"))
      (node (ref "C18") (pin "2") (pinfunction "2_2") (pintype "passive"))
      (node (ref "C19") (pin "2") (pinfunction "2_2") (pintype "passive"))
      (node (ref "C20") (pin "2") (pinfunction "2_2") (pintype "passive"))
      (node (ref "C21") (pin "2") (pinfunction "2_2") (pintype "passive"))
      (node (ref "C8") (pin "2") (pinfunction "2_2") (pintype "passive"))
      (node (ref "F2") (pin "2") (pinfunction "2_2") (pintype "passive"))
      (node (ref "FL1") (pin "2") (pinfunction "2_2") (pintype "passive"))
      (node (ref "FL2") (pin "1") (pinfunction "1_1") (pintype "passive"))
      (node (ref "R1") (pin "1") (pinfunction "1_1") (pintype "passive"))
      (node (ref "R12") (pin "2") (pinfunction "2_2") (pintype "passive"))
      (node (ref "R13") (pin "1") (pinfunction "1_1") (pintype "passive"))
      (node (ref "R15") (pin "2") (pinfunction "2_2") (pintype "passive"))
      (node (ref "R16") (pin "2") (pinfunction "2_2") (pintype "passive"))
      (node (ref "R17") (pin "2") (pinfunction "2_2") (pintype "passive"))
      (node (ref "R2") (pin "1") (pinfunction "1_1") (pintype "passive"))
      (node (ref "R3") (pin "1") (pinfunction "1_1") (pintype "passive"))
      (node (ref "R5") (pin "2") (pinfunction "2_2") (pintype "passive"))
      (node (ref "U2") (pin "13") (pinfunction "VCCINT_13") (pintype "power_in"))
      (node (ref "U2") (pin "31") (pinfunction "VCCIO1_31") (pintype "power_in"))
      (node (ref "U2") (pin "45") (pinfunction "VCCIO1_45") (pintype "power_in"))
      (node (ref "U2") (pin "59") (pinfunction "VCCIO2_59") (pintype "power_in"))
      (node (ref "U2") (pin "63") (pinfunction "VCCINT_63") (pintype "power_in"))
      (node (ref "U2") (pin "80") (pinfunction "VCCIO2_80") (pintype "power_in"))
      (node (ref "U2") (pin "9") (pinfunction "VCCIO1_9") (pintype "power_in"))
      (node (ref "U2") (pin "94") (pinfunction "VCCIO2_94") (pintype "power_in"))
    )
    (net (code "89") (name "unconnected-(A1-Pad5V)") (class "Default")
      (node (ref "A1") (pin "5V") (pinfunction "5V_5V") (pintype "power_in+no_connect"))
    )
    (net (code "90") (name "unconnected-(A1-PadAREF)") (class "Default")
      (node (ref "A1") (pin "AREF") (pinfunction "AREF_AREF") (pintype "bidirectional"))
    )
    (net (code "91") (name "unconnected-(A1-PadIOREF)") (class "Default")
      (node (ref "A1") (pin "IOREF") (pinfunction "IOREF_IOREF") (pintype "bidirectional"))
    )
    (net (code "92") (name "unconnected-(A1-PadP1)") (class "Default")
      (node (ref "A1") (pin "P1") (pinfunction "P1_P1") (pintype "bidirectional"))
    )
    (net (code "93") (name "unconnected-(A1-PadRST)") (class "Default")
      (node (ref "A1") (pin "RST") (pinfunction "RST_RST") (pintype "bidirectional"))
    )
    (net (code "94") (name "unconnected-(A1-PadVIN)") (class "Default")
      (node (ref "A1") (pin "VIN") (pinfunction "VIN_VIN") (pintype "power_in"))
    )
    (net (code "95") (name "unconnected-(A1D-AD4{slash}SDA-PadA4(SDA))") (class "Default")
      (node (ref "A1") (pin "A4(SDA)") (pinfunction "AD4/SDA_A4(SDA)") (pintype "bidirectional"))
    )
    (net (code "96") (name "unconnected-(A1D-AD5{slash}SCL-PadA5(SCL))") (class "Default")
      (node (ref "A1") (pin "A5(SCL)") (pinfunction "AD5/SCL_A5(SCL)") (pintype "bidirectional"))
    )
    (net (code "97") (name "unconnected-(J2-Pad6)") (class "Default")
      (node (ref "J2") (pin "6") (pinfunction "6_6") (pintype "passive"))
    )
    (net (code "98") (name "unconnected-(J2-Pad7)") (class "Default")
      (node (ref "J2") (pin "7") (pinfunction "7_7") (pintype "passive"))
    )
    (net (code "99") (name "unconnected-(J2-Pad8)") (class "Default")
      (node (ref "J2") (pin "8") (pinfunction "8_8") (pintype "passive"))
    )
    (net (code "100") (name "unconnected-(RN4-Pad3)") (class "Default")
      (node (ref "RN4") (pin "3") (pinfunction "3_3") (pintype "passive"))
    )
    (net (code "101") (name "unconnected-(RN4-Pad4)") (class "Default")
      (node (ref "RN4") (pin "4") (pinfunction "4_4") (pintype "passive"))
    )
    (net (code "102") (name "unconnected-(RN4-Pad5)") (class "Default")
      (node (ref "RN4") (pin "5") (pinfunction "5_5") (pintype "passive"))
    )
    (net (code "103") (name "unconnected-(RN4-Pad6)") (class "Default")
      (node (ref "RN4") (pin "6") (pinfunction "6_6") (pintype "passive"))
    )
    (net (code "104") (name "unconnected-(U2-IO_21-Pad21)") (class "Default")
      (node (ref "U2") (pin "21") (pinfunction "IO_21_21") (pintype "bidirectional"))
    )
    (net (code "105") (name "unconnected-(U2-IO_26-Pad26)") (class "Default")
      (node (ref "U2") (pin "26") (pinfunction "IO_26_26") (pintype "bidirectional"))
    )
    (net (code "106") (name "unconnected-(U2-IO_27-Pad27)") (class "Default")
      (node (ref "U2") (pin "27") (pinfunction "IO_27_27") (pintype "bidirectional"))
    )
    (net (code "107") (name "unconnected-(U2-IO_28-Pad28)") (class "Default")
      (node (ref "U2") (pin "28") (pinfunction "IO_28_28") (pintype "bidirectional"))
    )
    (net (code "108") (name "unconnected-(U2-IO_29-Pad29)") (class "Default")
      (node (ref "U2") (pin "29") (pinfunction "IO_29_29") (pintype "bidirectional"))
    )
    (net (code "109") (name "unconnected-(U2-IO_30-Pad30)") (class "Default")
      (node (ref "U2") (pin "30") (pinfunction "IO_30_30") (pintype "bidirectional"))
    )
    (net (code "110") (name "unconnected-(U2-IO_33-Pad33)") (class "Default")
      (node (ref "U2") (pin "33") (pinfunction "IO_33_33") (pintype "bidirectional"))
    )
    (net (code "111") (name "unconnected-(U2-IO_34-Pad34)") (class "Default")
      (node (ref "U2") (pin "34") (pinfunction "IO_34_34") (pintype "bidirectional"))
    )
    (net (code "112") (name "unconnected-(U2-IO_35-Pad35)") (class "Default")
      (node (ref "U2") (pin "35") (pinfunction "IO_35_35") (pintype "bidirectional"))
    )
    (net (code "113") (name "unconnected-(U2-IO_36-Pad36)") (class "Default")
      (node (ref "U2") (pin "36") (pinfunction "IO_36_36") (pintype "bidirectional"))
    )
    (net (code "114") (name "unconnected-(U2-IO_38-Pad38)") (class "Default")
      (node (ref "U2") (pin "38") (pinfunction "IO_38_38") (pintype "bidirectional"))
    )
    (net (code "115") (name "unconnected-(U2-IO_40-Pad40)") (class "Default")
      (node (ref "U2") (pin "40") (pinfunction "IO_40_40") (pintype "bidirectional"))
    )
    (net (code "116") (name "unconnected-(U2-IO_41-Pad41)") (class "Default")
      (node (ref "U2") (pin "41") (pinfunction "IO_41_41") (pintype "bidirectional"))
    )
    (net (code "117") (name "unconnected-(U2-IO_42-Pad42)") (class "Default")
      (node (ref "U2") (pin "42") (pinfunction "IO_42_42") (pintype "bidirectional"))
    )
    (net (code "118") (name "unconnected-(U2-IO_47-Pad47)") (class "Default")
      (node (ref "U2") (pin "47") (pinfunction "IO_47_47") (pintype "bidirectional"))
    )
    (net (code "119") (name "unconnected-(U2-IO_48-Pad48)") (class "Default")
      (node (ref "U2") (pin "48") (pinfunction "IO_48_48") (pintype "bidirectional"))
    )
    (net (code "120") (name "unconnected-(U2-IO_49-Pad49)") (class "Default")
      (node (ref "U2") (pin "49") (pinfunction "IO_49_49") (pintype "bidirectional"))
    )
    (net (code "121") (name "unconnected-(U2-IO_50-Pad50)") (class "Default")
      (node (ref "U2") (pin "50") (pinfunction "IO_50_50") (pintype "bidirectional"))
    )
    (net (code "122") (name "unconnected-(U2-IO_51-Pad51)") (class "Default")
      (node (ref "U2") (pin "51") (pinfunction "IO_51_51") (pintype "bidirectional"))
    )
    (net (code "123") (name "unconnected-(U2-IO_52-Pad52)") (class "Default")
      (node (ref "U2") (pin "52") (pinfunction "IO_52_52") (pintype "bidirectional"))
    )
    (net (code "124") (name "unconnected-(U2-IO_53-Pad53)") (class "Default")
      (node (ref "U2") (pin "53") (pinfunction "IO_53_53") (pintype "bidirectional"))
    )
    (net (code "125") (name "unconnected-(U2-IO_54-Pad54)") (class "Default")
      (node (ref "U2") (pin "54") (pinfunction "IO_54_54") (pintype "bidirectional"))
    )
    (net (code "126") (name "unconnected-(U2-IO_55-Pad55)") (class "Default")
      (node (ref "U2") (pin "55") (pinfunction "IO_55_55") (pintype "bidirectional"))
    )
    (net (code "127") (name "unconnected-(U2-IO_56-Pad56)") (class "Default")
      (node (ref "U2") (pin "56") (pinfunction "IO_56_56") (pintype "bidirectional"))
    )
    (net (code "128") (name "unconnected-(U2-IO_57-Pad57)") (class "Default")
      (node (ref "U2") (pin "57") (pinfunction "IO_57_57") (pintype "bidirectional"))
    )
    (net (code "129") (name "unconnected-(U2-IO_58-Pad58)") (class "Default")
      (node (ref "U2") (pin "58") (pinfunction "IO_58_58") (pintype "bidirectional"))
    )
    (net (code "130") (name "unconnected-(U2-IO_61-Pad61)") (class "Default")
      (node (ref "U2") (pin "61") (pinfunction "IO_61_61") (pintype "bidirectional"))
    )
    (net (code "131") (name "unconnected-(U2-IO_86-Pad86)") (class "Default")
      (node (ref "U2") (pin "86") (pinfunction "IO_86_86") (pintype "bidirectional"))
    )
    (net (code "132") (name "unconnected-(U2-IO_87-Pad87)") (class "Default")
      (node (ref "U2") (pin "87") (pinfunction "IO_87_87") (pintype "bidirectional"))
    )
    (net (code "133") (name "unconnected-(U2-IO_89-Pad89)") (class "Default")
      (node (ref "U2") (pin "89") (pinfunction "IO_89_89") (pintype "bidirectional"))
    )
    (net (code "134") (name "unconnected-(U2-IO_91-Pad91)") (class "Default")
      (node (ref "U2") (pin "91") (pinfunction "IO_91_91") (pintype "bidirectional"))
    )
    (net (code "135") (name "unconnected-(U2-IO_92-Pad92)") (class "Default")
      (node (ref "U2") (pin "92") (pinfunction "IO_92_92") (pintype "bidirectional"))
    )
    (net (code "136") (name "unconnected-(U2-IO_99-Pad99)") (class "Default")
      (node (ref "U2") (pin "99") (pinfunction "IO_99_99") (pintype "bidirectional"))
    )
    (net (code "137") (name "unconnected-(U2-IO_100-Pad100)") (class "Default")
      (node (ref "U2") (pin "100") (pinfunction "IO_100_100") (pintype "bidirectional"))
    )
    (net (code "138") (name "unconnected-(U2-IO{slash}DEV_OE-Pad43)") (class "Default")
      (node (ref "U2") (pin "43") (pinfunction "IO/DEV_OE_43") (pintype "bidirectional"))
    )
    (net (code "139") (name "unconnected-(U2-IO{slash}GCLK0-Pad12)") (class "Default")
      (node (ref "U2") (pin "12") (pinfunction "IO/GCLK0_12") (pintype "bidirectional"))
    )
    (net (code "140") (name "unconnected-(U2-IO{slash}GCLK1-Pad14)") (class "Default")
      (node (ref "U2") (pin "14") (pinfunction "IO/GCLK1_14") (pintype "bidirectional"))
    )
    (net (code "141") (name "unconnected-(U2-IO{slash}GCLK2-Pad62)") (class "Default")
      (node (ref "U2") (pin "62") (pinfunction "IO/GCLK2_62") (pintype "bidirectional"))
    )
    (net (code "142") (name "unconnected-(Y1-TRI_STATE-Pad1)") (class "Default")
      (node (ref "Y1") (pin "1") (pinfunction "TRI_STATE_1") (pintype "input+no_connect"))
    )
  )
)
